# LTEW_Power_Supply.net
KiCad netlist of a schematic drawn in Altium Designer
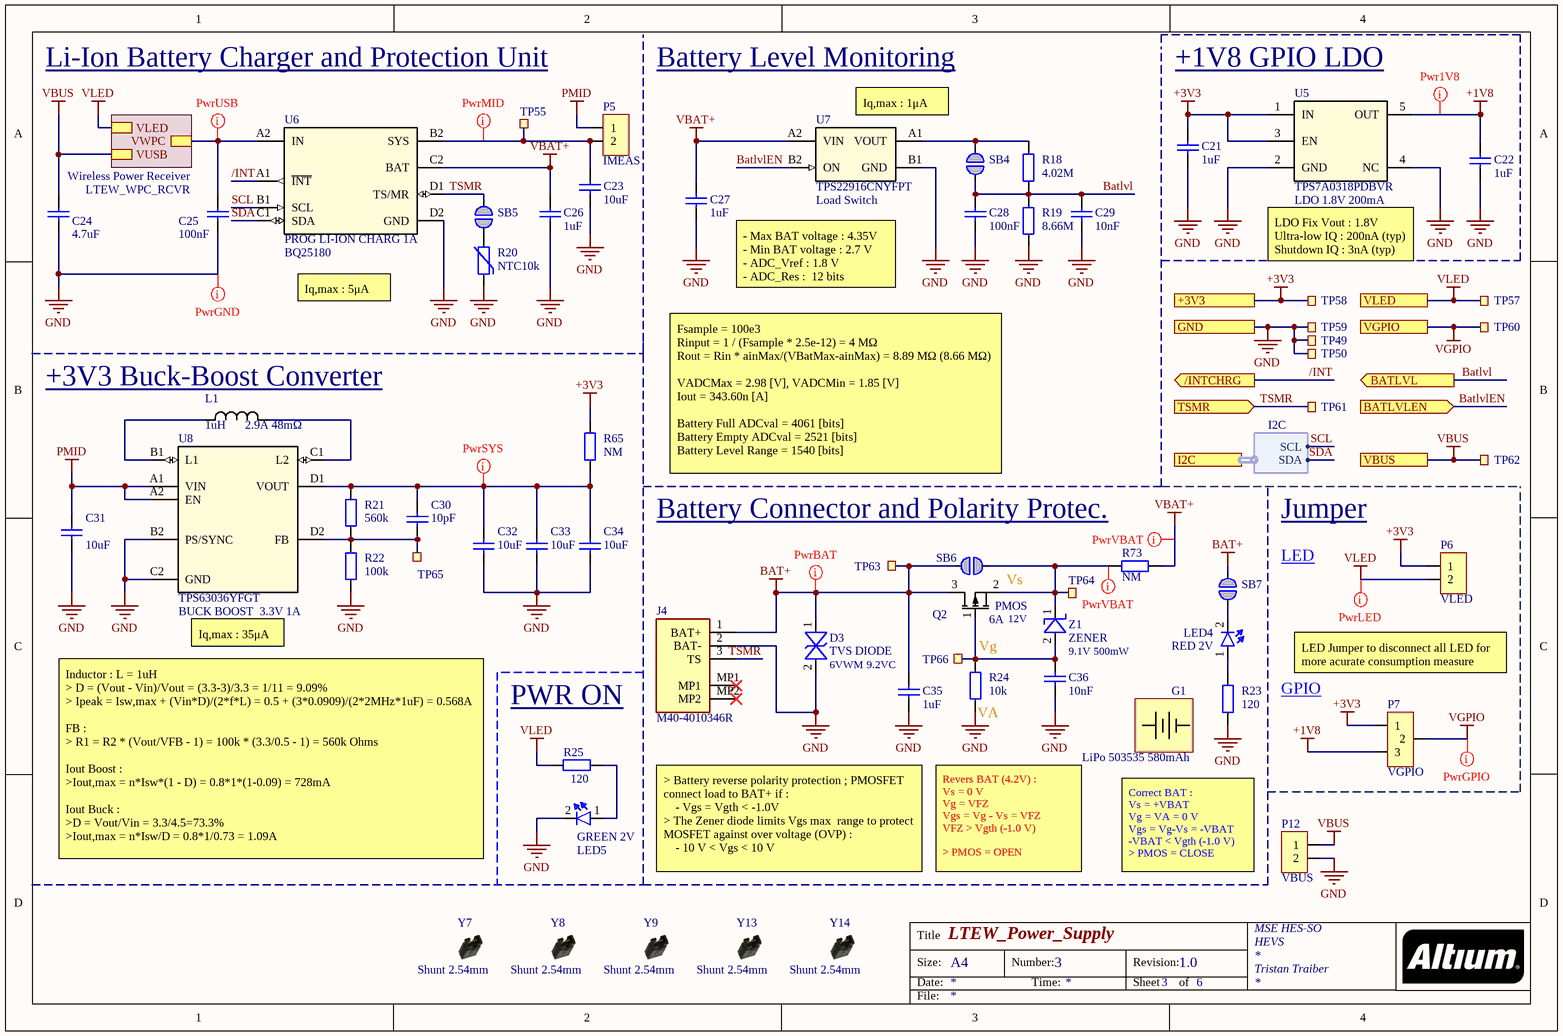
[diagram p0: LTEW_Power_Supply.SchDoc]

(export (version "E")
  (design (tool "Eeschema 10.0.6"))
  (components
    (comp (ref "C21")
      (value "1uF")
      (footprint "C0603")
      (description "1 µF ±10% 25V Ceramic Capacitor X7R 0603 (1608 Metric)")
      (fields (field (name "MANUFACTURER_PART_NUMBER") "CL10B105KA8NNNC"))
      (libsource (lib "LTEWlib") (part "C_1u"))
    )
    (comp (ref "C22")
      (value "1uF")
      (footprint "C0603")
      (description "1 µF ±10% 25V Ceramic Capacitor X7R 0603 (1608 Metric)")
      (fields (field (name "MANUFACTURER_PART_NUMBER") "CL10B105KA8NNNC"))
      (libsource (lib "LTEWlib") (part "C_1u"))
    )
    (comp (ref "C23")
      (value "10uF")
      (footprint "C0603")
      (description "10 µF ±10% 25V Ceramic Capacitor X5R 0805 (2012 Metric)")
      (fields (field (name "MANUFACTURER_PART_NUMBER") "GRM188R61E106KA73J"))
      (libsource (lib "LTEWlib") (part "C_10u"))
    )
    (comp (ref "C24")
      (value "4.7uF")
      (footprint "C0603")
      (description "4.7 µF ±10% 25V Condensateurs céramique X6S 0603 (1608 métrique)")
      (fields (field (name "MANUFACTURER_PART_NUMBER") "GRM188C81E475KE11D"))
      (libsource (lib "LTEWlib") (part "C_4.7u"))
    )
    (comp (ref "C25")
      (value "100nF")
      (footprint "C0603")
      (description "0.1 µF ±10% 25V Condensateurs céramique X7R 0603 (1608 métrique)")
      (fields (field (name "MANUFACTURER_PART_NUMBER") "CL10B104KA8NNNC"))
      (libsource (lib "LTEWlib") (part "C_100n"))
    )
    (comp (ref "C26")
      (value "1uF")
      (footprint "C0603")
      (description "1 µF ±10% 25V Ceramic Capacitor X7R 0603 (1608 Metric)")
      (fields (field (name "MANUFACTURER_PART_NUMBER") "CL10B105KA8NNNC"))
      (libsource (lib "LTEWlib") (part "C_1u"))
    )
    (comp (ref "C27")
      (value "1uF")
      (footprint "C0603")
      (description "1 µF ±10% 25V Ceramic Capacitor X7R 0603 (1608 Metric)")
      (fields (field (name "MANUFACTURER_PART_NUMBER") "CL10B105KA8NNNC"))
      (libsource (lib "LTEWlib") (part "C_1u"))
    )
    (comp (ref "C28")
      (value "100nF")
      (footprint "C0603")
      (description "0.1 µF ±10% 25V Condensateurs céramique X7R 0603 (1608 métrique)")
      (fields (field (name "MANUFACTURER_PART_NUMBER") "CL10B104KA8NNNC"))
      (libsource (lib "LTEWlib") (part "C_100n"))
    )
    (comp (ref "C29")
      (value "10nF")
      (footprint "C0603")
      (description "10000 pF ±5% 25V Condensateurs céramique C0G, NP0 0603 (1608 métrique)")
      (fields (field (name "MANUFACTURER_PART_NUMBER") "C1608C0G1E103J080AA"))
      (libsource (lib "LTEWlib") (part "C_10n"))
    )
    (comp (ref "C30")
      (value "10pF")
      (footprint "C0603")
      (description "10 pF ±5% 50V Ceramic Capacitor C0G, NP0 0603 (1608 Metric)")
      (fields (field (name "MANUFACTURER_PART_NUMBER") "06035A100JAT2A"))
      (libsource (lib "LTEWlib") (part "C_10p"))
    )
    (comp (ref "C31")
      (value "10uF")
      (footprint "C0603")
      (description "10 µF ±10% 25V Ceramic Capacitor X5R 0805 (2012 Metric)")
      (fields (field (name "MANUFACTURER_PART_NUMBER") "GRM188R61E106KA73J"))
      (libsource (lib "LTEWlib") (part "C_10u"))
    )
    (comp (ref "C32")
      (value "10uF")
      (footprint "C0603")
      (description "10 µF ±10% 25V Ceramic Capacitor X5R 0805 (2012 Metric)")
      (fields (field (name "MANUFACTURER_PART_NUMBER") "GRM188R61E106KA73J"))
      (libsource (lib "LTEWlib") (part "C_10u"))
    )
    (comp (ref "C33")
      (value "10uF")
      (footprint "C0603")
      (description "10 µF ±10% 25V Ceramic Capacitor X5R 0805 (2012 Metric)")
      (fields (field (name "MANUFACTURER_PART_NUMBER") "GRM188R61E106KA73J"))
      (libsource (lib "LTEWlib") (part "C_10u"))
    )
    (comp (ref "C34")
      (value "10uF")
      (footprint "C0603")
      (description "10 µF ±10% 25V Ceramic Capacitor X5R 0805 (2012 Metric)")
      (fields (field (name "MANUFACTURER_PART_NUMBER") "GRM188R61E106KA73J"))
      (libsource (lib "LTEWlib") (part "C_10u"))
    )
    (comp (ref "C35")
      (value "1uF")
      (footprint "C0603")
      (description "1 µF ±10% 25V Ceramic Capacitor X7R 0603 (1608 Metric)")
      (fields (field (name "MANUFACTURER_PART_NUMBER") "CL10B105KA8NNNC"))
      (libsource (lib "LTEWlib") (part "C_1u"))
    )
    (comp (ref "C36")
      (value "10nF")
      (footprint "C0603")
      (description "10000 pF ±5% 25V Condensateurs céramique C0G, NP0 0603 (1608 métrique)")
      (fields (field (name "MANUFACTURER_PART_NUMBER") "C1608C0G1E103J080AA"))
      (libsource (lib "LTEWlib") (part "C_10n"))
    )
    (comp (ref "D3")
      (value "TVS DIODE")
      (footprint "LTEWlib:SP100701ETG")
      (description "9.2V Clamp 5A (8/20µs) Ipp Tvs Diode Surface Mount SOD-882")
      (fields
        (field (name "MANUFACTURER_PART_NUMBER") "SP1007-01ETG")
        (field (name "ALTIUM_VALUE") "6VWM 9.2VC")
      )
      (libsource (lib "LTEWlib") (part "D_TVS"))
    )
    (comp (ref "G1")
      (value "LiPo 503535 580mAh")
      (footprint "Battery_Lipo_503535")
      (description "503535 3.8v 580mAh round lipo battery cells\r\n(Order : shorturl.at/tEFMZ)")
      (libsource (lib "LTEWlib") (part "Battery"))
    )
    (comp (ref "J4")
      (value "M40-4010346R")
      (footprint "LTEWlib:M404010346R")
      (description "Connector Header Surface Mount, Right Angle 3 position 0.039\" (1.00mm)")
      (fields (field (name "MOUSER PART NUMBER") "855-M40-4010346R"))
      (libsource (lib "LTEWlib") (part "CON_BAT_3POS"))
    )
    (comp (ref "L1")
      (value "2.9A 48mΩ")
      (footprint "1286ASH1R0MP2")
      (description "1 µH Shielded Drum Core, Wirewound Inductor 2.9 A 48mOhm Max 0806 (2016 Metric)")
      (fields
        (field (name "MANUFACTURER_PART_NUMBER") "DFE201612E-1R0M=P2")
        (field (name "ALTIUM_VALUE") "1uH")
        (field (name "COPYRIGHT") "Copyright (C) 2022 Ultra Librarian. All rights reserved.")
      )
      (libsource (lib "LTEWlib") (part "L_1u"))
    )
    (comp (ref "LED4")
      (value "RED 2V")
      (footprint "LTEWlib:LEDC1608X80N")
      (description "Red 625nm LED Indication - Discrete 2V 0603 (1608 Metric)")
      (fields (field (name "MANUFACTURER_PART_NUMBER") "150060RS75000"))
      (libsource (lib "LTEWlib") (part "LED_R"))
    )
    (comp (ref "LED5")
      (value "GREEN 2V")
      (footprint "LTEWlib:LEDC1608X80N")
      (description "Green 570nm LED Indication - Discrete 2V 0603 (1608 Metric)")
      (fields (field (name "MANUFACTURER_PART_NUMBER") "150060VS75000"))
      (libsource (lib "LTEWlib") (part "LED_G"))
    )
    (comp (ref "P5")
      (value "IMEAS")
      (footprint "HDR1X2 - IMEAS")
      (description "Header, 2-Pin")
      (fields (field (name "MANUFACTURER_PART_NUMBER") "10129378-902001BLF"))
      (libsource (lib "LTEWlib") (part "H_2POS"))
    )
    (comp (ref "P6")
      (value "VLED")
      (footprint "HDR1X2 - VLED")
      (description "Header, 2-Pin")
      (fields (field (name "MANUFACTURER_PART_NUMBER") "10129378-902001BLF"))
      (libsource (lib "LTEWlib") (part "H_2POS"))
    )
    (comp (ref "P7")
      (value "VGPIO")
      (footprint "HDR1X3 - VGPIO")
      (description "Header, 3-Pin")
      (fields (field (name "MANUFACTURER_PART_NUMBER") "M20-9990345"))
      (libsource (lib "LTEWlib") (part "H_3POS"))
    )
    (comp (ref "P12")
      (value "VBUS")
      (footprint "HDR1X2 - VIN")
      (description "Header, 2-Pin")
      (fields (field (name "MANUFACTURER_PART_NUMBER") "10129378-902001BLF"))
      (libsource (lib "") (part "H_2POS_1"))
    )
    (comp (ref "Q2")
      (value "PMOS")
      (footprint "LTEWlib:SSM3J332RLFT")
      (description "P-Channel 12 V 6A (Ta) 1W (Ta) Surface Mount SOT-23F")
      (fields
        (field (name "MANUFACTURER_PART_NUMBER") "SSM3J338R")
        (field (name "VALUE2") "6A")
        (field (name "ALTIUM_VALUE") "12V")
      )
      (libsource (lib "LTEWlib") (part "MOS-P"))
    )
    (comp (ref "R18")
      (value "4.02M")
      (footprint "RES0603")
      (fields (field (name "MANUFACTURER_PART_NUMBER") "RC0603FR-074M02L"))
      (libsource (lib "LTEWlib") (part "R_4M"))
    )
    (comp (ref "R19")
      (value "8.66M")
      (footprint "RES0603")
      (description "8.66 MOhms ±1% 0,1W, 1/10W Pavé résistif 0603 (1608 métrique) AutomobileAEC-Q200 Couche épaisse")
      (fields (field (name "MANUFACTURER_PART_NUMBER") "CRCW06038M66FKEA"))
      (libsource (lib "") (part "R_8.66M_1"))
    )
    (comp (ref "R20")
      (value "NTC10k")
      (footprint "C0603")
      (description "NTC Thermistor 10k 0603 (1608 Metric)")
      (fields (field (name "MANUFACTURER_PART_NUMBER") "ERT-J1VR103J"))
      (libsource (lib "LTEWlib") (part "R_NTC_10k"))
    )
    (comp (ref "R21")
      (value "560k")
      (footprint "RES0603")
      (fields (field (name "MANUFACTURER_PART_NUMBER") "AC0603FR-07560KL"))
      (libsource (lib "LTEWlib") (part "R_560k"))
    )
    (comp (ref "R22")
      (value "100k")
      (footprint "RES0603")
      (description "RES SMD 100K OHM 1% 1/8W 0603")
      (fields (field (name "MANUFACTURER_PART_NUMBER") "RC0805FR-07100KL"))
      (libsource (lib "LTEWlib") (part "R_100k"))
    )
    (comp (ref "R23")
      (value "120")
      (footprint "RES0603")
      (description "1 MOhms ±1% 0.1W, 1/10W Chip Resistor 0603 (1608 Metric) Automotive AEC-Q200 Thick Film")
      (fields (field (name "MANUFACTURER_PART_NUMBER") "CRGCQ0603F120R"))
      (libsource (lib "") (part "R_120_1"))
    )
    (comp (ref "R24")
      (value "10k")
      (footprint "RES0603")
      (description "10 kOhms ±1% 0.1W, 1/10W Chip Resistor 0603 (1608 Metric) Moisture Resistant Thick Film")
      (fields (field (name "MANUFACTURER_PART_NUMBER") "RC0805FR-0710KL"))
      (libsource (lib "LTEWlib") (part "R_10k"))
    )
    (comp (ref "R25")
      (value "120")
      (footprint "RES0603")
      (description "1 MOhms ±1% 0.1W, 1/10W Chip Resistor 0603 (1608 Metric) Automotive AEC-Q200 Thick Film")
      (fields (field (name "MANUFACTURER_PART_NUMBER") "CRGCQ0603F120R"))
      (libsource (lib "LTEWlib") (part "R_120"))
    )
    (comp (ref "R65")
      (value "NM")
      (footprint "RES0603")
      (description "8.66 MOhms ±1% 0,1W, 1/10W Pavé résistif 0603 (1608 métrique) AutomobileAEC-Q200 Couche épaisse")
      (fields (field (name "MANUFACTURER_PART_NUMBER") "CRCW06038M66FKEA"))
      (libsource (lib "") (part "R_8.66M_1"))
    )
    (comp (ref "R73")
      (value "NM")
      (footprint "RES0603")
      (description "8.66 MOhms ±1% 0,1W, 1/10W Pavé résistif 0603 (1608 métrique) AutomobileAEC-Q200 Couche épaisse")
      (fields (field (name "MANUFACTURER_PART_NUMBER") "CRCW06038M66FKEA"))
      (libsource (lib "LTEWlib") (part "R_8.66M"))
    )
    (comp (ref "SB4")
      (value "Solderbridge")
      (footprint "Solderbridge")
      (fields (field (name "MANUFACTURER") "N.A."))
      (libsource (lib "pca10090") (part "Solderbridge"))
    )
    (comp (ref "SB5")
      (value "Solderbridge")
      (footprint "Solderbridge")
      (fields (field (name "MANUFACTURER") "N.A."))
      (libsource (lib "pca10090") (part "Solderbridge"))
    )
    (comp (ref "SB6")
      (value "Solderbridge")
      (footprint "Solderbridge")
      (fields (field (name "MANUFACTURER") "N.A."))
      (libsource (lib "pca10090") (part "Solderbridge"))
    )
    (comp (ref "SB7")
      (value "Solderbridge")
      (footprint "Solderbridge")
      (fields (field (name "MANUFACTURER") "N.A."))
      (libsource (lib "pca10090") (part "Solderbridge"))
    )
    (comp (ref "TP49")
      (value "Ø1.0mm,SMD")
      (footprint "TP_SMD_Ø0.8mm")
      (description "0.8 mm circular SMD testpad")
      (fields
        (field (name "PART NUMBER") "TP_SMD_Ø1.0MM")
        (field (name "MANUFACTURER") "Nordic Semiconductor")
      )
      (libsource (lib "LTEWlib") (part "TP_SMD"))
    )
    (comp (ref "TP50")
      (value "Ø1.0mm,SMD")
      (footprint "TP_SMD_Ø0.8mm")
      (description "0.8 mm circular SMD testpad")
      (fields
        (field (name "PART NUMBER") "TP_SMD_Ø1.0MM")
        (field (name "MANUFACTURER") "Nordic Semiconductor")
      )
      (libsource (lib "LTEWlib") (part "TP_SMD"))
    )
    (comp (ref "TP55")
      (value "Ø1.0mm,SMD")
      (footprint "TP_SMD_Ø0.8mm")
      (description "0.8 mm circular SMD testpad")
      (fields
        (field (name "PART NUMBER") "TP_SMD_Ø1.0MM")
        (field (name "MANUFACTURER") "Nordic Semiconductor")
      )
      (libsource (lib "") (part "TP_SMD_3"))
    )
    (comp (ref "TP57")
      (value "Ø1.0mm,SMD")
      (footprint "TP_SMD_Ø0.8mm")
      (description "0.8 mm circular SMD testpad")
      (fields
        (field (name "PART NUMBER") "TP_SMD_Ø1.0MM")
        (field (name "MANUFACTURER") "Nordic Semiconductor")
      )
      (libsource (lib "LTEWlib") (part "TP_SMD"))
    )
    (comp (ref "TP58")
      (value "Ø1.0mm,SMD")
      (footprint "TP_SMD_Ø0.8mm")
      (description "0.8 mm circular SMD testpad")
      (fields
        (field (name "PART NUMBER") "TP_SMD_Ø1.0MM")
        (field (name "MANUFACTURER") "Nordic Semiconductor")
      )
      (libsource (lib "LTEWlib") (part "TP_SMD"))
    )
    (comp (ref "TP59")
      (value "Ø1.0mm,SMD")
      (footprint "TP_SMD_Ø0.8mm")
      (description "0.8 mm circular SMD testpad")
      (fields
        (field (name "PART NUMBER") "TP_SMD_Ø1.0MM")
        (field (name "MANUFACTURER") "Nordic Semiconductor")
      )
      (libsource (lib "LTEWlib") (part "TP_SMD"))
    )
    (comp (ref "TP60")
      (value "Ø1.0mm,SMD")
      (footprint "TP_SMD_Ø0.8mm")
      (description "0.8 mm circular SMD testpad")
      (fields
        (field (name "PART NUMBER") "TP_SMD_Ø1.0MM")
        (field (name "MANUFACTURER") "Nordic Semiconductor")
      )
      (libsource (lib "LTEWlib") (part "TP_SMD"))
    )
    (comp (ref "TP61")
      (value "Ø1.0mm,SMD")
      (footprint "TP_SMD_Ø0.8mm")
      (description "0.8 mm circular SMD testpad")
      (fields
        (field (name "PART NUMBER") "TP_SMD_Ø1.0MM")
        (field (name "MANUFACTURER") "Nordic Semiconductor")
      )
      (libsource (lib "LTEWlib") (part "TP_SMD"))
    )
    (comp (ref "TP62")
      (value "Ø1.0mm,SMD")
      (footprint "TP_SMD_Ø0.8mm")
      (description "0.8 mm circular SMD testpad")
      (fields
        (field (name "PART NUMBER") "TP_SMD_Ø1.0MM")
        (field (name "MANUFACTURER") "Nordic Semiconductor")
      )
      (libsource (lib "LTEWlib") (part "TP_SMD"))
    )
    (comp (ref "TP63")
      (value "Ø1.0mm,SMD")
      (footprint "TP_SMD_Ø0.8mm")
      (description "0.8 mm circular SMD testpad")
      (fields
        (field (name "PART NUMBER") "TP_SMD_Ø1.0MM")
        (field (name "MANUFACTURER") "Nordic Semiconductor")
      )
      (libsource (lib "") (part "TP_SMD_2"))
    )
    (comp (ref "TP64")
      (value "Ø1.0mm,SMD")
      (footprint "TP_SMD_Ø0.8mm")
      (description "0.8 mm circular SMD testpad")
      (fields
        (field (name "PART NUMBER") "TP_SMD_Ø1.0MM")
        (field (name "MANUFACTURER") "Nordic Semiconductor")
      )
      (libsource (lib "LTEWlib") (part "TP_SMD"))
    )
    (comp (ref "TP65")
      (value "Ø1.0mm,SMD")
      (footprint "TP_SMD_Ø0.8mm")
      (description "0.8 mm circular SMD testpad")
      (fields
        (field (name "PART NUMBER") "TP_SMD_Ø1.0MM")
        (field (name "MANUFACTURER") "Nordic Semiconductor")
      )
      (libsource (lib "") (part "TP_SMD_1"))
    )
    (comp (ref "TP66")
      (value "Ø1.0mm,SMD")
      (footprint "TP_SMD_Ø0.8mm")
      (description "0.8 mm circular SMD testpad")
      (fields
        (field (name "PART NUMBER") "TP_SMD_Ø1.0MM")
        (field (name "MANUFACTURER") "Nordic Semiconductor")
      )
      (libsource (lib "") (part "TP_SMD_2"))
    )
    (comp (ref "U5")
      (value "TPS7A0318PDBVR")
      (footprint "SOT95P280X145-5N")
      (description "Linear Voltage Regulator IC Positive Fixed 1 Output 200mA SOT-23-5")
      (fields
        (field (name "MANUFACTURER_PART_NUMBER") "TPS7A0312PDBVR")
        (field (name "ALTIUM_VALUE") "LDO 1.8V 200mA")
        (field (name "COPYRIGHT") "Copyright (C) 2022 Ultra Librarian. All rights reserved.")
      )
      (libsource (lib "LTEWlib") (part "IC_TPS7A0318PDBVR"))
    )
    (comp (ref "U6")
      (value "BQ25180")
      (footprint "LTEWlib:BGA8C40P2X4_100X155X50")
      (description "Charger IC Lithium Ion/Polymer, Lithium Iron Phosphate 8-DSBGA")
      (fields
        (field (name "MANUFACTURER_PART_NUMBER") "BQ25180YBGR")
        (field (name "ALTIUM_VALUE") "PROG LI-ION CHARG 1A")
        (field (name "COPYRIGHT") "Copyright (C) 2022 Ultra Librarian. All rights reserved.")
      )
      (libsource (lib "LTEWlib") (part "IC_BQ25180YBGT"))
    )
    (comp (ref "U7")
      (value "TPS22916CNYFPT")
      (footprint "BGA4C40P2X2_78X78X50")
      (description "Power Switch/Driver 1:1 P-Channel 2A 4-DSBGA")
      (fields
        (field (name "ALTIUM_VALUE") "Load Switch")
        (field (name "COPYRIGHT") "Copyright (C) 2022 Ultra Librarian. All rights reserved.")
      )
      (libsource (lib "LTEWlib") (part "SW_LOAD_SW"))
    )
    (comp (ref "U8")
      (value "TPS63036YFGT")
      (footprint "BGA8C40P2X4_108X181X62")
      (description "Buck-Boost Switching Regulator IC Positive Adjustable 1.2V 1 Output 1A (Switch) 8-UFBGA, DSBGA")
      (fields
        (field (name "ALTIUM_VALUE") "BUCK BOOST  3.3V 1A")
        (field (name "COPYRIGHT") "Copyright (C) 2022 Ultra Librarian. All rights reserved.")
      )
      (libsource (lib "LTEWlib") (part "IC_TPS63036YFGT"))
    )
    (comp (ref "Y7")
      (value "Shunt 2.54mm")
      (footprint "Shunt_2.54mm_Horizontal")
      (description "Shunt Jumper 2.54mm Black")
      (fields (field (name "MANUFACTURER PART NUMBER") "SPC02SYAN"))
      (libsource (lib "LTEWlib") (part "SHUNT JUMPER 2.54mm BLACK GOLD Horizontal"))
    )
    (comp (ref "Y8")
      (value "Shunt 2.54mm")
      (footprint "Shunt_2.54mm_Horizontal")
      (description "Shunt Jumper 2.54mm Black")
      (fields (field (name "MANUFACTURER PART NUMBER") "SPC02SYAN"))
      (libsource (lib "LTEWlib") (part "SHUNT JUMPER 2.54mm BLACK GOLD Horizontal"))
    )
    (comp (ref "Y9")
      (value "Shunt 2.54mm")
      (footprint "Shunt_2.54mm_Horizontal")
      (description "Shunt Jumper 2.54mm Black")
      (fields (field (name "MANUFACTURER PART NUMBER") "SPC02SYAN"))
      (libsource (lib "LTEWlib") (part "SHUNT JUMPER 2.54mm BLACK GOLD Horizontal"))
    )
    (comp (ref "Y13")
      (value "Shunt 2.54mm")
      (footprint "Shunt_2.54mm_Horizontal")
      (description "Shunt Jumper 2.54mm Black")
      (fields (field (name "MANUFACTURER PART NUMBER") "SPC02SYAN"))
      (libsource (lib "LTEWlib") (part "SHUNT JUMPER 2.54mm BLACK GOLD Horizontal"))
    )
    (comp (ref "Y14")
      (value "Shunt 2.54mm")
      (footprint "Shunt_2.54mm_Horizontal")
      (description "Shunt Jumper 2.54mm Black")
      (fields (field (name "MANUFACTURER PART NUMBER") "SPC02SYAN"))
      (libsource (lib "LTEWlib") (part "SHUNT JUMPER 2.54mm BLACK GOLD Horizontal"))
    )
    (comp (ref "Z1")
      (value "ZENER")
      (footprint "LTEWlib:SOD3716X145N")
      (description "Zener Diode 9.1 V 500 mW ±6% Surface Mount SOD-123")
      (fields
        (field (name "MANUFACTURER_PART_NUMBER") "BZT52C9V1S-7-F")
        (field (name "ALTIUM_VALUE") "9.1V 500mW")
      )
      (libsource (lib "LTEWlib") (part "D_ZENER_9V1"))
    )
  )
  (nets
    (net (code "2") (name "+1V8") (class "Default")
      (node (ref "C22") (pin "2") (pinfunction "2_2") (pintype "passive"))
      (node (ref "P7") (pin "3") (pinfunction "3_3") (pintype "passive"))
      (node (ref "U5") (pin "5") (pinfunction "OUT_5") (pintype "passive"))
    )
    (net (code "3") (name "+3V3") (class "Default")
      (node (ref "C21") (pin "2") (pinfunction "2_2") (pintype "passive"))
      (node (ref "P6") (pin "1") (pinfunction "1_1") (pintype "passive"))
      (node (ref "P7") (pin "1") (pinfunction "1_1") (pintype "passive"))
      (node (ref "R65") (pin "2") (pinfunction "2_2") (pintype "passive"))
      (node (ref "TP58") (pin "1") (pinfunction "1_1") (pintype "passive"))
      (node (ref "U5") (pin "1") (pinfunction "IN_1") (pintype "passive"))
      (node (ref "U5") (pin "3") (pinfunction "EN_3") (pintype "passive"))
    )
    (net (code "4") (name "/Batlvl") (class "Default")
      (node (ref "C28") (pin "2") (pinfunction "2_2") (pintype "passive"))
      (node (ref "C29") (pin "2") (pinfunction "2_2") (pintype "passive"))
      (node (ref "R18") (pin "1") (pinfunction "1_1") (pintype "passive"))
      (node (ref "R19") (pin "2") (pinfunction "2_2") (pintype "passive"))
      (node (ref "SB4") (pin "2") (pinfunction "1_2") (pintype "passive"))
    )
    (net (code "5") (name "/BatlvlEN") (class "Default")
      (node (ref "U7") (pin "B2") (pinfunction "ON_B2") (pintype "input"))
    )
    (net (code "6") (name "/SCL") (class "Default")
      (node (ref "U6") (pin "B1") (pinfunction "SCL_B1") (pintype "input"))
    )
    (net (code "7") (name "/SDA") (class "Default")
      (node (ref "U6") (pin "C1") (pinfunction "SDA_C1") (pintype "bidirectional"))
    )
    (net (code "8") (name "/TSMR") (class "Default")
      (node (ref "J4") (pin "3") (pinfunction "TS_3") (pintype "passive"))
      (node (ref "SB5") (pin "1") (pinfunction "0_1") (pintype "passive"))
      (node (ref "TP61") (pin "1") (pinfunction "1_1") (pintype "passive"))
      (node (ref "U6") (pin "D1") (pinfunction "TS/MR_D1") (pintype "bidirectional"))
    )
    (net (code "9") (name "/VWPC") (class "Default")
      (node (ref "C25") (pin "2") (pinfunction "2_2") (pintype "passive"))
      (node (ref "U6") (pin "A2") (pinfunction "IN_A2") (pintype "power_in"))
    )
    (net (code "11") (name "/{slash}INT") (class "Default")
      (node (ref "U6") (pin "A1") (pinfunction "~{INT}_A1") (pintype "output"))
    )
    (net (code "12") (name "BAT+") (class "Default")
      (node (ref "C35") (pin "2") (pinfunction "2_2") (pintype "passive"))
      (node (ref "D3") (pin "1") (pinfunction "1_1") (pintype "passive"))
      (node (ref "J4") (pin "1") (pinfunction "BAT+_1") (pintype "passive"))
      (node (ref "Q2") (pin "3") (pinfunction "D_3") (pintype "passive"))
      (node (ref "SB6") (pin "1") (pinfunction "0_1") (pintype "passive"))
      (node (ref "SB7") (pin "1") (pinfunction "0_1") (pintype "passive"))
      (node (ref "TP63") (pin "1") (pinfunction "1_1") (pintype "passive"))
    )
    (net (code "13") (name "GND") (class "Default")
      (node (ref "C21") (pin "1") (pinfunction "1_1") (pintype "passive"))
      (node (ref "C22") (pin "1") (pinfunction "1_1") (pintype "passive"))
      (node (ref "C23") (pin "1") (pinfunction "1_1") (pintype "passive"))
      (node (ref "C24") (pin "2") (pinfunction "2_2") (pintype "passive"))
      (node (ref "C25") (pin "1") (pinfunction "1_1") (pintype "passive"))
      (node (ref "C26") (pin "1") (pinfunction "1_1") (pintype "passive"))
      (node (ref "C27") (pin "1") (pinfunction "1_1") (pintype "passive"))
      (node (ref "C28") (pin "1") (pinfunction "1_1") (pintype "passive"))
      (node (ref "C29") (pin "1") (pinfunction "1_1") (pintype "passive"))
      (node (ref "C31") (pin "1") (pinfunction "1_1") (pintype "passive"))
      (node (ref "C32") (pin "1") (pinfunction "1_1") (pintype "passive"))
      (node (ref "C33") (pin "1") (pinfunction "1_1") (pintype "passive"))
      (node (ref "C34") (pin "1") (pinfunction "1_1") (pintype "passive"))
      (node (ref "C35") (pin "1") (pinfunction "1_1") (pintype "passive"))
      (node (ref "C36") (pin "1") (pinfunction "1_1") (pintype "passive"))
      (node (ref "D3") (pin "2") (pinfunction "2_2") (pintype "passive"))
      (node (ref "J4") (pin "2") (pinfunction "BAT-_2") (pintype "passive"))
      (node (ref "LED5") (pin "2") (pinfunction "K_2") (pintype "passive"))
      (node (ref "P12") (pin "2") (pinfunction "2_2") (pintype "passive"))
      (node (ref "R19") (pin "1") (pinfunction "1_1") (pintype "passive"))
      (node (ref "R20") (pin "1") (pinfunction "1_1") (pintype "passive"))
      (node (ref "R22") (pin "1") (pinfunction "1_1") (pintype "passive"))
      (node (ref "R23") (pin "1") (pinfunction "1_1") (pintype "passive"))
      (node (ref "R24") (pin "1") (pinfunction "1_1") (pintype "passive"))
      (node (ref "TP49") (pin "1") (pinfunction "1_1") (pintype "passive"))
      (node (ref "TP50") (pin "1") (pinfunction "1_1") (pintype "passive"))
      (node (ref "TP59") (pin "1") (pinfunction "1_1") (pintype "passive"))
      (node (ref "U5") (pin "2") (pinfunction "GND_2") (pintype "passive"))
      (node (ref "U5") (pin "4") (pinfunction "NC_4") (pintype "passive"))
      (node (ref "U6") (pin "D2") (pinfunction "GND_D2") (pintype "power_in"))
      (node (ref "U7") (pin "B1") (pinfunction "GND_B1") (pintype "power_in"))
      (node (ref "U8") (pin "B2") (pinfunction "PS/SYNC_B2") (pintype "passive"))
      (node (ref "U8") (pin "C2") (pinfunction "GND_C2") (pintype "passive"))
    )
    (net (code "14") (name "Net-(LED4-A)") (class "Default")
      (node (ref "LED4") (pin "1") (pinfunction "A_1") (pintype "passive"))
      (node (ref "R23") (pin "2") (pinfunction "2_2") (pintype "passive"))
    )
    (net (code "15") (name "Net-(LED4-K)") (class "Default")
      (node (ref "LED4") (pin "2") (pinfunction "K_2") (pintype "passive"))
      (node (ref "SB7") (pin "2") (pinfunction "1_2") (pintype "passive"))
    )
    (net (code "16") (name "Net-(LED5-A)") (class "Default")
      (node (ref "LED5") (pin "1") (pinfunction "A_1") (pintype "passive"))
      (node (ref "R25") (pin "2") (pinfunction "2_2") (pintype "passive"))
    )
    (net (code "17") (name "Net-(Q2-G)") (class "Default")
      (node (ref "C36") (pin "2") (pinfunction "2_2") (pintype "passive"))
      (node (ref "Q2") (pin "1") (pinfunction "G_1") (pintype "passive"))
      (node (ref "R24") (pin "2") (pinfunction "2_2") (pintype "passive"))
      (node (ref "TP66") (pin "1") (pinfunction "1_1") (pintype "passive"))
      (node (ref "Z1") (pin "2") (pinfunction "A_2") (pintype "passive"))
    )
    (net (code "18") (name "Net-(Q2-S)") (class "Default")
      (node (ref "Q2") (pin "2") (pinfunction "S_2") (pintype "passive"))
      (node (ref "R73") (pin "2") (pinfunction "2_2") (pintype "passive"))
      (node (ref "SB6") (pin "2") (pinfunction "1_2") (pintype "passive"))
      (node (ref "TP64") (pin "1") (pinfunction "1_1") (pintype "passive"))
      (node (ref "Z1") (pin "1") (pinfunction "K_1") (pintype "passive"))
    )
    (net (code "19") (name "Net-(SB4-0)") (class "Default")
      (node (ref "R18") (pin "2") (pinfunction "2_2") (pintype "passive"))
      (node (ref "SB4") (pin "1") (pinfunction "0_1") (pintype "passive"))
      (node (ref "U7") (pin "A1") (pinfunction "VOUT_A1") (pintype "power_in"))
    )
    (net (code "20") (name "Net-(SB5-1)") (class "Default")
      (node (ref "R20") (pin "2") (pinfunction "2_2") (pintype "passive"))
      (node (ref "SB5") (pin "2") (pinfunction "1_2") (pintype "passive"))
    )
    (net (code "21") (name "Net-(U6-SYS)") (class "Default")
      (node (ref "C23") (pin "2") (pinfunction "2_2") (pintype "passive"))
      (node (ref "P5") (pin "2") (pinfunction "2_2") (pintype "passive"))
      (node (ref "TP55") (pin "1") (pinfunction "1_1") (pintype "passive"))
      (node (ref "U6") (pin "B2") (pinfunction "SYS_B2") (pintype "power_in"))
    )
    (net (code "22") (name "Net-(U8-FB)") (class "Default")
      (node (ref "C30") (pin "1") (pinfunction "1_1") (pintype "passive"))
      (node (ref "R21") (pin "1") (pinfunction "1_1") (pintype "passive"))
      (node (ref "R22") (pin "2") (pinfunction "2_2") (pintype "passive"))
      (node (ref "TP65") (pin "1") (pinfunction "1_1") (pintype "passive"))
      (node (ref "U8") (pin "D2") (pinfunction "FB_D2") (pintype "passive"))
    )
    (net (code "23") (name "Net-(U8-L1)") (class "Default")
      (node (ref "L1") (pin "2") (pinfunction "2_2") (pintype "passive"))
      (node (ref "U8") (pin "B1") (pinfunction "L1_B1") (pintype "bidirectional"))
    )
    (net (code "24") (name "Net-(U8-L2)") (class "Default")
      (node (ref "L1") (pin "1") (pinfunction "1_1") (pintype "passive"))
      (node (ref "U8") (pin "C1") (pinfunction "L2_C1") (pintype "bidirectional"))
    )
    (net (code "25") (name "Net-(U8-VOUT)") (class "Default")
      (node (ref "C30") (pin "2") (pinfunction "2_2") (pintype "passive"))
      (node (ref "C32") (pin "2") (pinfunction "2_2") (pintype "passive"))
      (node (ref "C33") (pin "2") (pinfunction "2_2") (pintype "passive"))
      (node (ref "C34") (pin "2") (pinfunction "2_2") (pintype "passive"))
      (node (ref "R21") (pin "2") (pinfunction "2_2") (pintype "passive"))
      (node (ref "R65") (pin "1") (pinfunction "1_1") (pintype "passive"))
      (node (ref "U8") (pin "D1") (pinfunction "VOUT_D1") (pintype "power_in"))
    )
    (net (code "26") (name "PMID") (class "Default")
      (node (ref "C31") (pin "2") (pinfunction "2_2") (pintype "passive"))
      (node (ref "P5") (pin "1") (pinfunction "1_1") (pintype "passive"))
      (node (ref "U8") (pin "A1") (pinfunction "VIN_A1") (pintype "power_in"))
      (node (ref "U8") (pin "A2") (pinfunction "EN_A2") (pintype "passive"))
    )
    (net (code "27") (name "VBAT+") (class "Default")
      (node (ref "C26") (pin "2") (pinfunction "2_2") (pintype "passive"))
      (node (ref "C27") (pin "2") (pinfunction "2_2") (pintype "passive"))
      (node (ref "R73") (pin "1") (pinfunction "1_1") (pintype "passive"))
      (node (ref "U6") (pin "C2") (pinfunction "BAT_C2") (pintype "power_in"))
      (node (ref "U7") (pin "A2") (pinfunction "VIN_A2") (pintype "power_in"))
    )
    (net (code "28") (name "VBUS") (class "Default")
      (node (ref "C24") (pin "1") (pinfunction "1_1") (pintype "passive"))
      (node (ref "P12") (pin "1") (pinfunction "1_1") (pintype "passive"))
      (node (ref "TP62") (pin "1") (pinfunction "1_1") (pintype "passive"))
    )
    (net (code "29") (name "VGPIO") (class "Default")
      (node (ref "P7") (pin "2") (pinfunction "2_2") (pintype "passive"))
      (node (ref "TP60") (pin "1") (pinfunction "1_1") (pintype "passive"))
    )
    (net (code "30") (name "VLED") (class "Default")
      (node (ref "P6") (pin "2") (pinfunction "2_2") (pintype "passive"))
      (node (ref "R25") (pin "1") (pinfunction "1_1") (pintype "passive"))
      (node (ref "TP57") (pin "1") (pinfunction "1_1") (pintype "passive"))
    )
    (net (code "31") (name "unconnected-(J4-PadMP1)") (class "Default")
      (node (ref "J4") (pin "MP1") (pinfunction "MP1_MP1") (pintype "passive+no_connect"))
    )
    (net (code "32") (name "unconnected-(J4-PadMP2)") (class "Default")
      (node (ref "J4") (pin "MP2") (pinfunction "MP2_MP2") (pintype "passive+no_connect"))
    )
  )
)
